# TL201_LED.net
KiCad netlist of a schematic drawn in Altium Designer
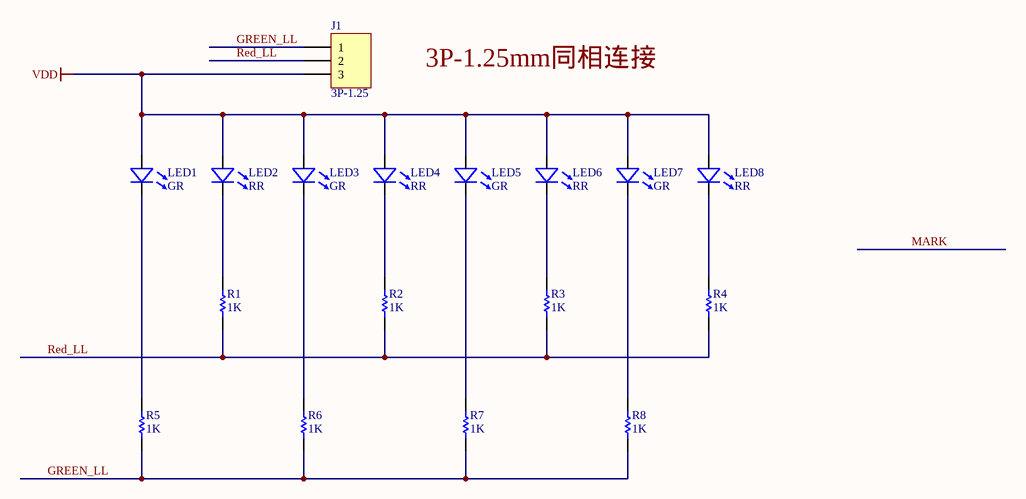
[diagram p0: TL201蓝牙LED显示.SchDoc]

(export (version "E")
  (design (tool "Eeschema 10.0.6"))
  (components
    (comp (ref "J1")
      (value "3P-1.25")
      (footprint "3P-1.25")
      (description "Header, 3-Pin")
      (fields (field (name "PUBLISHER") "Altium Limited"))
      (libsource (lib "Miscellaneous Connectors") (part "Header 3"))
    )
    (comp (ref "LED1") (value "GR") (footprint "0603LED") (libsource (lib "MyLibrary") (part "LED")))
    (comp (ref "LED2") (value "RR") (footprint "0603LED") (libsource (lib "MyLibrary") (part "LED")))
    (comp (ref "LED3") (value "GR") (footprint "0603LED") (libsource (lib "MyLibrary") (part "LED")))
    (comp (ref "LED4") (value "RR") (footprint "0603LED") (libsource (lib "MyLibrary") (part "LED")))
    (comp (ref "LED5") (value "GR") (footprint "0603LED") (libsource (lib "MyLibrary") (part "LED")))
    (comp (ref "LED6") (value "RR") (footprint "0603LED") (libsource (lib "MyLibrary") (part "LED")))
    (comp (ref "LED7") (value "GR") (footprint "0603LED") (libsource (lib "MyLibrary") (part "LED")))
    (comp (ref "LED8") (value "RR") (footprint "0603LED") (libsource (lib "MyLibrary") (part "LED")))
    (comp (ref "R1")
      (value "1K")
      (footprint "R0603")
      (description "Resistor")
      (fields (field (name "PUBLISHER") "Altium Limited"))
      (libsource (lib "Miscellaneous Devices") (part "Res1"))
    )
    (comp (ref "R2")
      (value "1K")
      (footprint "R0603")
      (description "Resistor")
      (fields (field (name "PUBLISHER") "Altium Limited"))
      (libsource (lib "Miscellaneous Devices") (part "Res1"))
    )
    (comp (ref "R3")
      (value "1K")
      (footprint "R0603")
      (description "Resistor")
      (fields (field (name "PUBLISHER") "Altium Limited"))
      (libsource (lib "Miscellaneous Devices") (part "Res1"))
    )
    (comp (ref "R4")
      (value "1K")
      (footprint "R0603")
      (description "Resistor")
      (fields (field (name "PUBLISHER") "Altium Limited"))
      (libsource (lib "Miscellaneous Devices") (part "Res1"))
    )
    (comp (ref "R5")
      (value "1K")
      (footprint "R0603")
      (description "Resistor")
      (fields (field (name "PUBLISHER") "Altium Limited"))
      (libsource (lib "Miscellaneous Devices") (part "Res1"))
    )
    (comp (ref "R6")
      (value "1K")
      (footprint "R0603")
      (description "Resistor")
      (fields (field (name "PUBLISHER") "Altium Limited"))
      (libsource (lib "Miscellaneous Devices") (part "Res1"))
    )
    (comp (ref "R7")
      (value "1K")
      (footprint "R0603")
      (description "Resistor")
      (fields (field (name "PUBLISHER") "Altium Limited"))
      (libsource (lib "Miscellaneous Devices") (part "Res1"))
    )
    (comp (ref "R8")
      (value "1K")
      (footprint "R0603")
      (description "Resistor")
      (fields (field (name "PUBLISHER") "Altium Limited"))
      (libsource (lib "Miscellaneous Devices") (part "Res1"))
    )
  )
  (nets
    (net (code "1") (name "/GREEN_LL") (class "Default")
      (node (ref "J1") (pin "1") (pinfunction "1_1") (pintype "passive"))
      (node (ref "R5") (pin "2") (pinfunction "2_2") (pintype "passive"))
      (node (ref "R6") (pin "2") (pinfunction "2_2") (pintype "passive"))
      (node (ref "R7") (pin "2") (pinfunction "2_2") (pintype "passive"))
      (node (ref "R8") (pin "2") (pinfunction "2_2") (pintype "passive"))
    )
    (net (code "3") (name "/Red_LL") (class "Default")
      (node (ref "J1") (pin "2") (pinfunction "2_2") (pintype "passive"))
      (node (ref "R1") (pin "2") (pinfunction "2_2") (pintype "passive"))
      (node (ref "R2") (pin "2") (pinfunction "2_2") (pintype "passive"))
      (node (ref "R3") (pin "2") (pinfunction "2_2") (pintype "passive"))
      (node (ref "R4") (pin "2") (pinfunction "2_2") (pintype "passive"))
    )
    (net (code "4") (name "Net-(LED1-k)") (class "Default")
      (node (ref "LED1") (pin "2") (pinfunction "k_2") (pintype "passive"))
      (node (ref "R5") (pin "1") (pinfunction "1_1") (pintype "passive"))
    )
    (net (code "5") (name "Net-(LED2-k)") (class "Default")
      (node (ref "LED2") (pin "2") (pinfunction "k_2") (pintype "passive"))
      (node (ref "R1") (pin "1") (pinfunction "1_1") (pintype "passive"))
    )
    (net (code "6") (name "Net-(LED3-k)") (class "Default")
      (node (ref "LED3") (pin "2") (pinfunction "k_2") (pintype "passive"))
      (node (ref "R6") (pin "1") (pinfunction "1_1") (pintype "passive"))
    )
    (net (code "7") (name "Net-(LED4-k)") (class "Default")
      (node (ref "LED4") (pin "2") (pinfunction "k_2") (pintype "passive"))
      (node (ref "R2") (pin "1") (pinfunction "1_1") (pintype "passive"))
    )
    (net (code "8") (name "Net-(LED5-k)") (class "Default")
      (node (ref "LED5") (pin "2") (pinfunction "k_2") (pintype "passive"))
      (node (ref "R7") (pin "1") (pinfunction "1_1") (pintype "passive"))
    )
    (net (code "9") (name "Net-(LED6-k)") (class "Default")
      (node (ref "LED6") (pin "2") (pinfunction "k_2") (pintype "passive"))
      (node (ref "R3") (pin "1") (pinfunction "1_1") (pintype "passive"))
    )
    (net (code "10") (name "Net-(LED7-k)") (class "Default")
      (node (ref "LED7") (pin "2") (pinfunction "k_2") (pintype "passive"))
      (node (ref "R8") (pin "1") (pinfunction "1_1") (pintype "passive"))
    )
    (net (code "11") (name "Net-(LED8-k)") (class "Default")
      (node (ref "LED8") (pin "2") (pinfunction "k_2") (pintype "passive"))
      (node (ref "R4") (pin "1") (pinfunction "1_1") (pintype "passive"))
    )
    (net (code "12") (name "VDD") (class "Default")
      (node (ref "J1") (pin "3") (pinfunction "3_3") (pintype "passive"))
      (node (ref "LED1") (pin "1") (pinfunction "a_1") (pintype "passive"))
      (node (ref "LED2") (pin "1") (pinfunction "a_1") (pintype "passive"))
      (node (ref "LED3") (pin "1") (pinfunction "a_1") (pintype "passive"))
      (node (ref "LED4") (pin "1") (pinfunction "a_1") (pintype "passive"))
      (node (ref "LED5") (pin "1") (pinfunction "a_1") (pintype "passive"))
      (node (ref "LED6") (pin "1") (pinfunction "a_1") (pintype "passive"))
      (node (ref "LED7") (pin "1") (pinfunction "a_1") (pintype "passive"))
      (node (ref "LED8") (pin "1") (pinfunction "a_1") (pintype "passive"))
    )
  )
)
